# logi-cam.net
KiCad netlist of a schematic drawn in Altium Designer
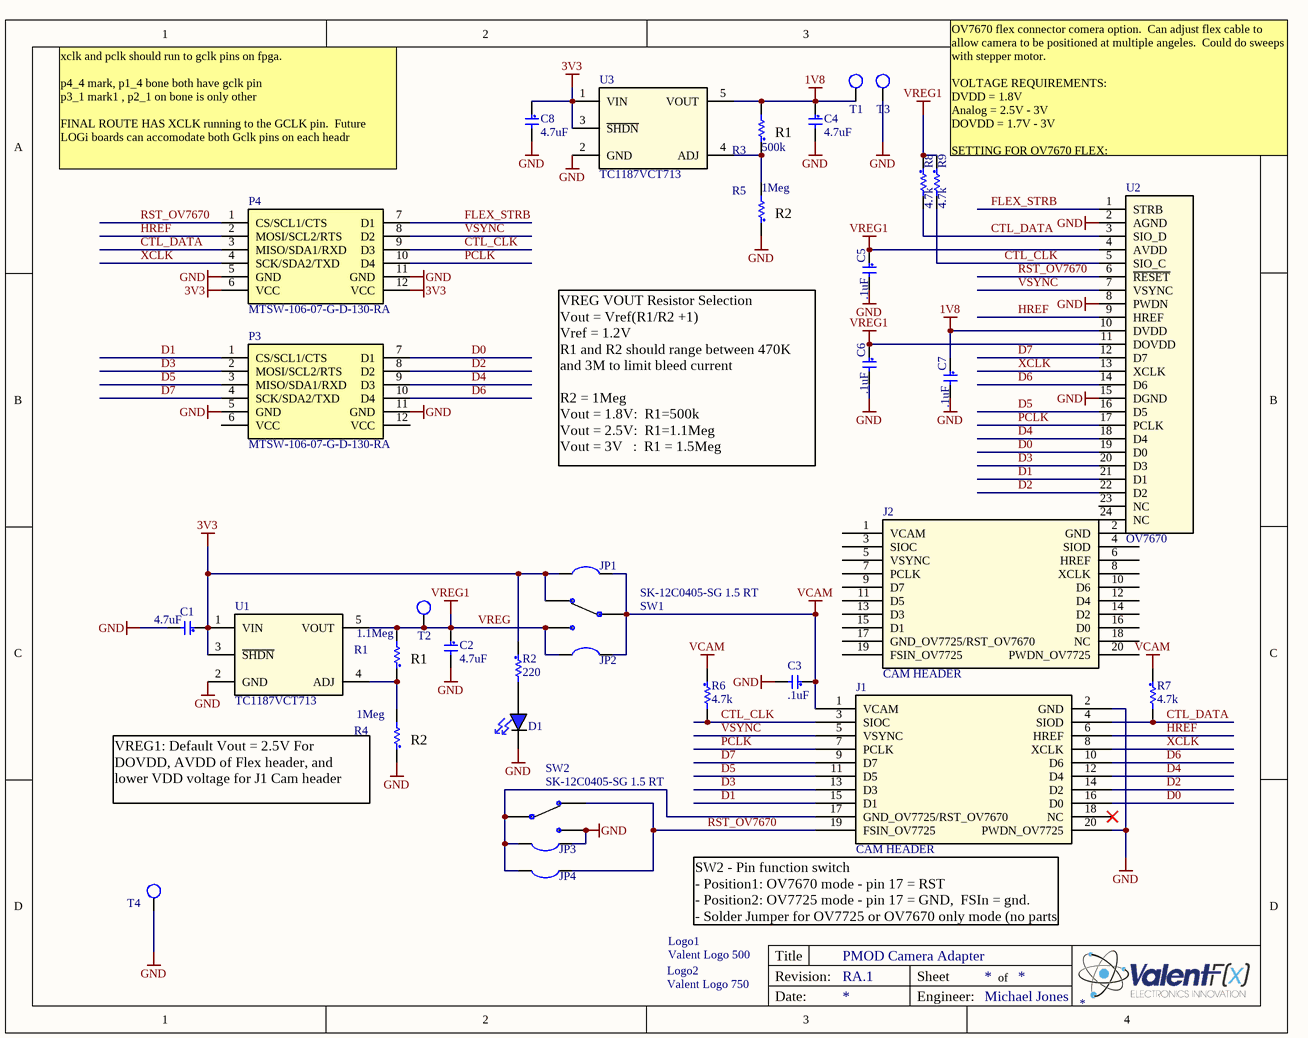
[diagram p0: logi-cam.SchDoc]

(export (version "E")
  (design (tool "Eeschema 10.0.6"))
  (components
    (comp (ref "C1")
      (value "4.7uF")
      (footprint "mRCL:C0603")
      (description "4.7uF 10volts Y5V +80-20% (MLCC) - SMD/SMT 0603")
      (fields
        (field (name "MANUFACTURER") "Murata")
        (field (name "MANUFACTURER PART NUMBER") "GRM188F51A475ZE20D")
      )
      (libsource (lib "mCapacitors") (part "C0603 - GRM188F51A475ZE20D"))
    )
    (comp (ref "C2")
      (value "4.7uF")
      (footprint "mRCL:C0603")
      (description "4.7uF 10volts Y5V +80-20% (MLCC) - SMD/SMT 0603")
      (fields
        (field (name "MANUFACTURER") "Murata")
        (field (name "MANUFACTURER PART NUMBER") "GRM188F51A475ZE20D")
      )
      (libsource (lib "mCapacitors") (part "C0603 - GRM188F51A475ZE20D"))
    )
    (comp (ref "C3")
      (value ".1uF")
      (footprint "mRCL:C0603")
      (description ".10uF X7R 20% (MLCC) - SMD/SMT 0603 25volts")
      (fields (field (name "MANUFACTURER") "TDK") (field (name "MANUFACTURER PART NUMBER") "C1608X7R1E104MT"))
      (libsource (lib "mCapacitors") (part "C0603 - C1608X7R1E104MT"))
    )
    (comp (ref "C4")
      (value "4.7uF")
      (footprint "mRCL:C0603")
      (description "4.7uF 10volts Y5V +80-20% (MLCC) - SMD/SMT 0603")
      (fields
        (field (name "MANUFACTURER") "Murata")
        (field (name "MANUFACTURER PART NUMBER") "GRM188F51A475ZE20D")
      )
      (libsource (lib "mCapacitors") (part "C0603 - GRM188F51A475ZE20D"))
    )
    (comp (ref "C5")
      (value ".1uF")
      (footprint "mRCL:C0603")
      (description ".10uF X7R 20% (MLCC) - SMD/SMT 0603 25volts")
      (fields (field (name "MANUFACTURER") "TDK") (field (name "MANUFACTURER PART NUMBER") "C1608X7R1E104MT"))
      (libsource (lib "mCapacitors") (part "C0603 - C1608X7R1E104MT"))
    )
    (comp (ref "C6")
      (value ".1uF")
      (footprint "mRCL:C0603")
      (description ".10uF X7R 20% (MLCC) - SMD/SMT 0603 25volts")
      (fields (field (name "MANUFACTURER") "TDK") (field (name "MANUFACTURER PART NUMBER") "C1608X7R1E104MT"))
      (libsource (lib "mCapacitors") (part "C0603 - C1608X7R1E104MT"))
    )
    (comp (ref "C7")
      (value ".1uF")
      (footprint "mRCL:C0603")
      (description ".10uF X7R 20% (MLCC) - SMD/SMT 0603 25volts")
      (fields (field (name "MANUFACTURER") "TDK") (field (name "MANUFACTURER PART NUMBER") "C1608X7R1E104MT"))
      (libsource (lib "mCapacitors") (part "C0603 - C1608X7R1E104MT"))
    )
    (comp (ref "C8")
      (value "4.7uF")
      (footprint "mRCL:C0603")
      (description "4.7uF 10volts Y5V +80-20% (MLCC) - SMD/SMT 0603")
      (fields
        (field (name "MANUFACTURER") "Murata")
        (field (name "MANUFACTURER PART NUMBER") "GRM188F51A475ZE20D")
      )
      (libsource (lib "mCapacitors") (part "C0603 - GRM188F51A475ZE20D"))
    )
    (comp (ref "D1")
      (value "BLUE LED0603")
      (footprint "LED_0603 - BLUE")
      (description "BLUE Standard LED - SMD Blue 470nm 40mcd 20mA")
      (fields
        (field (name "MANUFACTURER") "Harvatek International")
        (field (name "MANUFACTURER PART NUMBER") "HT-193NB-5589")
      )
      (libsource (lib "mDiode") (part "LED0603 - HT-193NB-5589"))
    )
    (comp (ref "J1")
      (value "CAM HEADER")
      (footprint "HEADER_10x2_40_100 1-3-5 THRU DIP")
      (description "CMOS CAMERA HEADER")
      (libsource (lib "mModule") (part "CAM - DUAL CAMERA HEADER_1"))
    )
    (comp (ref "J2")
      (value "CAM HEADER")
      (footprint "HEADER_10x2_40_100 1-3-5 THRU DIP")
      (description "CMOS CAMERA HEADER")
      (libsource (lib "mModule") (part "CAM - DUAL CAMERA HEADER_1"))
    )
    (comp (ref "JP1")
      (value "Solder Jumper")
      (footprint "SOLDER_JUMPER")
      (description "Solder/Configuration Jumper")
      (fields (field (name "MANUFACTURER") "n/a"))
      (libsource (lib "mConnector") (part "Solder Jumper"))
    )
    (comp (ref "JP2")
      (value "Solder Jumper")
      (footprint "SOLDER_JUMPER")
      (description "Solder/Configuration Jumper")
      (fields (field (name "MANUFACTURER") "n/a"))
      (libsource (lib "mConnector") (part "Solder Jumper"))
    )
    (comp (ref "JP3")
      (value "Solder Jumper")
      (footprint "SOLDER_JUMPER")
      (description "Solder/Configuration Jumper")
      (fields (field (name "MANUFACTURER") "n/a"))
      (libsource (lib "mConnector") (part "Solder Jumper"))
    )
    (comp (ref "JP4")
      (value "Solder Jumper")
      (footprint "SOLDER_JUMPER")
      (description "Solder/Configuration Jumper")
      (fields (field (name "MANUFACTURER") "n/a"))
      (libsource (lib "mConnector") (part "Solder Jumper"))
    )
    (comp (ref "Logo1")
      (value "Valent Logo 500")
      (footprint "ValentFX_500")
      (libsource (lib "mLogos") (part "Valent Logo 500"))
    )
    (comp (ref "Logo2")
      (value "Valent Logo 750")
      (footprint "ValentFX_750")
      (libsource (lib "mLogos") (part "Valent Logo 750"))
    )
    (comp (ref "P3")
      (value "MTSW-106-07-G-D-130-RA")
      (footprint "mconnector:PMOD HEADER - Male")
      (description "Samtec Male Conn Unshrouded Header HDR 12 POS 2.54mm Solder RA Thru-Hole")
      (fields (field (name "MANUFACTURER") "Samtec"))
      (libsource (lib "mConnector") (part "P-MOD - MTSW-106-07-G-D-130-RA"))
    )
    (comp (ref "P4")
      (value "MTSW-106-07-G-D-130-RA")
      (footprint "mconnector:PMOD HEADER - Male")
      (description "Samtec Male Conn Unshrouded Header HDR 12 POS 2.54mm Solder RA Thru-Hole")
      (fields (field (name "MANUFACTURER") "Samtec"))
      (libsource (lib "mConnector") (part "P-MOD - MTSW-106-07-G-D-130-RA"))
    )
    (comp (ref "R1")
      (value "1.1Meg")
      (footprint "R0805")
      (description "1Kohms 1% Thick Film Resistors - SMD 0603  Tol")
      (fields
        (field (name "MANUFACTURER") "Panasonic Electronic Components")
        (field (name "MANUFACTURER PART NUMBER") "ERJ-3EKF1001V")
      )
      (libsource (lib "mResistors") (part "R0603 - ERJ-3EKF1001V"))
    )
    (comp (ref "R2")
      (value "220")
      (footprint "mRCL:R0603")
      (description "220 - thick Film Resistors - SMD 0603 220ohms 1% Tol")
      (fields
        (field (name "MANUFACTURER") "Panasonic - ECG")
        (field (name "MANUFACTURER PART NUMBER") "ERJ-3EKF2200V")
      )
      (libsource (lib "mResistors") (part "R0603 - ERJ-3EKF2200V"))
    )
    (comp (ref "R3")
      (value "500k")
      (footprint "R0805")
      (description "1Kohms 1% Thick Film Resistors - SMD 0603  Tol")
      (fields
        (field (name "MANUFACTURER") "Panasonic Electronic Components")
        (field (name "MANUFACTURER PART NUMBER") "ERJ-3EKF1001V")
      )
      (libsource (lib "mResistors") (part "R0603 - ERJ-3EKF1001V"))
    )
    (comp (ref "R4")
      (value "1Meg")
      (footprint "R0805")
      (description "1Kohms 1% Thick Film Resistors - SMD 0603  Tol")
      (fields
        (field (name "MANUFACTURER") "Panasonic Electronic Components")
        (field (name "MANUFACTURER PART NUMBER") "ERJ-3EKF1001V")
      )
      (libsource (lib "mResistors") (part "R0603 - ERJ-3EKF1001V"))
    )
    (comp (ref "R5")
      (value "1Meg")
      (footprint "R0805")
      (description "1Kohms 1% Thick Film Resistors - SMD 0603  Tol")
      (fields
        (field (name "MANUFACTURER") "Panasonic Electronic Components")
        (field (name "MANUFACTURER PART NUMBER") "ERJ-3EKF1001V")
      )
      (libsource (lib "mResistors") (part "R0603 - ERJ-3EKF1001V"))
    )
    (comp (ref "R6")
      (value "4.7k")
      (footprint "mRCL:R0603")
      (description "4.7k Thick Film Resistors - SMD 1/10watt 4.7Kohms 1%")
      (fields
        (field (name "MANUFACTURER") "Vishay Dale")
        (field (name "MANUFACTURER PART NUMBER") "CRCW06034K70FKEA")
      )
      (libsource (lib "mResistors") (part "R0603 - CRCW06034K70FKEA"))
    )
    (comp (ref "R7")
      (value "4.7k")
      (footprint "mRCL:R0603")
      (description "4.7k Thick Film Resistors - SMD 1/10watt 4.7Kohms 1%")
      (fields
        (field (name "MANUFACTURER") "Vishay Dale")
        (field (name "MANUFACTURER PART NUMBER") "CRCW06034K70FKEA")
      )
      (libsource (lib "mResistors") (part "R0603 - CRCW06034K70FKEA"))
    )
    (comp (ref "R8")
      (value "4.7k")
      (footprint "mRCL:R0603")
      (description "4.7k Thick Film Resistors - SMD 1/10watt 4.7Kohms 1%")
      (fields
        (field (name "MANUFACTURER") "Vishay Dale")
        (field (name "MANUFACTURER PART NUMBER") "CRCW06034K70FKEA")
      )
      (libsource (lib "mResistors") (part "R0603 - CRCW06034K70FKEA"))
    )
    (comp (ref "R9")
      (value "4.7k")
      (footprint "mRCL:R0603")
      (description "4.7k Thick Film Resistors - SMD 1/10watt 4.7Kohms 1%")
      (fields
        (field (name "MANUFACTURER") "Vishay Dale")
        (field (name "MANUFACTURER PART NUMBER") "CRCW06034K70FKEA")
      )
      (libsource (lib "mResistors") (part "R0603 - CRCW06034K70FKEA"))
    )
    (comp (ref "SW1")
      (value "SK-12C0405-SG 1.5 RT")
      (footprint "SW - SK-12C0405-SG 1.5 RT")
      (description "Slide Switches SPDT 0.3 Amp at 4 V")
      (fields (field (name "MANUFACTURER") "C&K Components"))
      (libsource (lib "mElectroMechanical") (part "SW - SK-12C0405-SG 1.5 RT"))
    )
    (comp (ref "SW2")
      (value "SK-12C0405-SG 1.5 RT")
      (footprint "SW - SK-12C0405-SG 1.5 RT")
      (description "Slide Switches SPDT 0.3 Amp at 4 V")
      (fields (field (name "MANUFACTURER") "C&K Components"))
      (libsource (lib "mElectroMechanical") (part "SW - SK-12C0405-SG 1.5 RT"))
    )
    (comp (ref "T1")
      (value "Test Point")
      (footprint "Tp 25-40")
      (description "Test Point Smaller Symbol")
      (libsource (lib "mConnector") (part "Test Point 2"))
    )
    (comp (ref "T2")
      (value "Test Point")
      (footprint "Tp 25-40")
      (description "Test Point Smaller Symbol")
      (libsource (lib "mConnector") (part "Test Point 2"))
    )
    (comp (ref "T3")
      (value "Test Point")
      (footprint "Tp 25-40")
      (description "Test Point Smaller Symbol")
      (libsource (lib "mConnector") (part "Test Point 2"))
    )
    (comp (ref "T4")
      (value "Test Point")
      (footprint "Tp 25-40")
      (description "Test Point Smaller Symbol")
      (libsource (lib "mConnector") (part "Test Point 2"))
    )
    (comp (ref "U1")
      (value "TC1187VCT713")
      (footprint "SOT95P280X145-5N - TC2054")
      (description "IC REG LDO ADJ .15A SOT23A-5")
      (fields (field (name "MANUFACTURER") "Microchip Technology"))
      (libsource (lib "mIC") (part "REG - TC1187VCT713"))
    )
    (comp (ref "U2")
      (value "OV7670")
      (footprint "OV7670")
      (description "OV7670 - 24 PIN FFC")
      (libsource (lib "mModule") (part "OV7670"))
    )
    (comp (ref "U3")
      (value "TC1187VCT713")
      (footprint "SOT95P280X145-5N - TC2054")
      (description "IC REG LDO ADJ .15A SOT23A-5")
      (fields (field (name "MANUFACTURER") "Microchip Technology"))
      (libsource (lib "mIC") (part "REG - TC1187VCT713"))
    )
  )
  (nets
    (net (code "1") (name "/CTL_CLK") (class "Default")
      (node (ref "J1") (pin "3") (pinfunction "SIOC_3") (pintype "passive"))
      (node (ref "P4") (pin "9") (pinfunction "D3_9") (pintype "power_in"))
      (node (ref "R6") (pin "2") (pinfunction "2_2") (pintype "passive"))
      (node (ref "R9") (pin "2") (pinfunction "2_2") (pintype "passive"))
      (node (ref "U2") (pin "5") (pinfunction "SIO_C_5") (pintype "passive"))
    )
    (net (code "2") (name "/CTL_DATA") (class "Default")
      (node (ref "J1") (pin "4") (pinfunction "SIOD_4") (pintype "passive"))
      (node (ref "P4") (pin "3") (pinfunction "MISO/SDA1/RXD_3") (pintype "power_in"))
      (node (ref "R7") (pin "2") (pinfunction "2_2") (pintype "passive"))
      (node (ref "R8") (pin "2") (pinfunction "2_2") (pintype "passive"))
      (node (ref "U2") (pin "3") (pinfunction "SIO_D_3") (pintype "passive"))
    )
    (net (code "3") (name "/D0") (class "Default")
      (node (ref "J1") (pin "16") (pinfunction "D0_16") (pintype "passive"))
      (node (ref "P3") (pin "7") (pinfunction "D1_7") (pintype "power_in"))
      (node (ref "U2") (pin "19") (pinfunction "D0_19") (pintype "passive"))
    )
    (net (code "4") (name "/D1") (class "Default")
      (node (ref "J1") (pin "15") (pinfunction "D1_15") (pintype "passive"))
      (node (ref "P3") (pin "1") (pinfunction "CS/SCL1/CTS_1") (pintype "power_in"))
      (node (ref "U2") (pin "21") (pinfunction "D1_21") (pintype "passive"))
    )
    (net (code "5") (name "/D2") (class "Default")
      (node (ref "J1") (pin "14") (pinfunction "D2_14") (pintype "passive"))
      (node (ref "P3") (pin "8") (pinfunction "D2_8") (pintype "power_in"))
      (node (ref "U2") (pin "22") (pinfunction "D2_22") (pintype "passive"))
    )
    (net (code "6") (name "/D3") (class "Default")
      (node (ref "J1") (pin "13") (pinfunction "D3_13") (pintype "passive"))
      (node (ref "P3") (pin "2") (pinfunction "MOSI/SCL2/RTS_2") (pintype "power_in"))
      (node (ref "U2") (pin "20") (pinfunction "D3_20") (pintype "passive"))
    )
    (net (code "7") (name "/D4") (class "Default")
      (node (ref "J1") (pin "12") (pinfunction "D4_12") (pintype "passive"))
      (node (ref "P3") (pin "9") (pinfunction "D3_9") (pintype "power_in"))
      (node (ref "U2") (pin "18") (pinfunction "D4_18") (pintype "passive"))
    )
    (net (code "8") (name "/D5") (class "Default")
      (node (ref "J1") (pin "11") (pinfunction "D5_11") (pintype "passive"))
      (node (ref "P3") (pin "3") (pinfunction "MISO/SDA1/RXD_3") (pintype "power_in"))
      (node (ref "U2") (pin "16") (pinfunction "D5_16") (pintype "passive"))
    )
    (net (code "9") (name "/D6") (class "Default")
      (node (ref "J1") (pin "10") (pinfunction "D6_10") (pintype "passive"))
      (node (ref "P3") (pin "10") (pinfunction "D4_10") (pintype "power_in"))
      (node (ref "U2") (pin "14") (pinfunction "D6_14") (pintype "passive"))
    )
    (net (code "10") (name "/D7") (class "Default")
      (node (ref "J1") (pin "9") (pinfunction "D7_9") (pintype "passive"))
      (node (ref "P3") (pin "4") (pinfunction "SCK/SDA2/TXD_4") (pintype "power_in"))
      (node (ref "U2") (pin "12") (pinfunction "D7_12") (pintype "passive"))
    )
    (net (code "11") (name "/FLEX_STRB") (class "Default")
      (node (ref "P4") (pin "7") (pinfunction "D1_7") (pintype "power_in"))
      (node (ref "U2") (pin "1") (pinfunction "STRB_1") (pintype "passive"))
    )
    (net (code "12") (name "/HREF") (class "Default")
      (node (ref "J1") (pin "6") (pinfunction "HREF_6") (pintype "passive"))
      (node (ref "P4") (pin "2") (pinfunction "MOSI/SCL2/RTS_2") (pintype "power_in"))
      (node (ref "U2") (pin "9") (pinfunction "HREF_9") (pintype "passive"))
    )
    (net (code "13") (name "/PCLK") (class "Default")
      (node (ref "J1") (pin "7") (pinfunction "PCLK_7") (pintype "passive"))
      (node (ref "P4") (pin "10") (pinfunction "D4_10") (pintype "power_in"))
      (node (ref "U2") (pin "17") (pinfunction "PCLK_17") (pintype "passive"))
    )
    (net (code "14") (name "/RST_OV7670") (class "Default")
      (node (ref "J1") (pin "19") (pinfunction "FSIN_OV7725_19") (pintype "passive"))
      (node (ref "JP4") (pin "1") (pinfunction "1_1") (pintype "passive"))
      (node (ref "P4") (pin "1") (pinfunction "CS/SCL1/CTS_1") (pintype "power_in"))
      (node (ref "SW2") (pin "2") (pinfunction "2_2") (pintype "passive"))
      (node (ref "U2") (pin "6") (pinfunction "~{RESET}_6") (pintype "passive"))
    )
    (net (code "15") (name "/VSYNC") (class "Default")
      (node (ref "J1") (pin "5") (pinfunction "VSYNC_5") (pintype "passive"))
      (node (ref "P4") (pin "8") (pinfunction "D2_8") (pintype "power_in"))
      (node (ref "U2") (pin "7") (pinfunction "VSYNC_7") (pintype "passive"))
    )
    (net (code "16") (name "/XCLK") (class "Default")
      (node (ref "J1") (pin "8") (pinfunction "XCLK_8") (pintype "passive"))
      (node (ref "P4") (pin "4") (pinfunction "SCK/SDA2/TXD_4") (pintype "power_in"))
      (node (ref "U2") (pin "13") (pinfunction "XCLK_13") (pintype "passive"))
    )
    (net (code "17") (name "1V8") (class "Default")
      (node (ref "C4") (pin "1") (pinfunction "1_1") (pintype "passive"))
      (node (ref "C7") (pin "1") (pinfunction "1_1") (pintype "passive"))
      (node (ref "R3") (pin "2") (pinfunction "2_2") (pintype "passive"))
      (node (ref "T1") (pin "1") (pinfunction "1_1") (pintype "passive"))
      (node (ref "U2") (pin "10") (pinfunction "DVDD_10") (pintype "passive"))
      (node (ref "U3") (pin "5") (pinfunction "VOUT_5") (pintype "passive"))
    )
    (net (code "18") (name "3V3") (class "Default")
      (node (ref "C1") (pin "1") (pinfunction "1_1") (pintype "passive"))
      (node (ref "C8") (pin "1") (pinfunction "1_1") (pintype "passive"))
      (node (ref "JP1") (pin "1") (pinfunction "1_1") (pintype "passive"))
      (node (ref "P4") (pin "12") (pinfunction "VCC_12") (pintype "power_in"))
      (node (ref "P4") (pin "6") (pinfunction "VCC_6") (pintype "power_in"))
      (node (ref "R2") (pin "1") (pinfunction "1_1") (pintype "passive"))
      (node (ref "SW1") (pin "2") (pinfunction "2_2") (pintype "passive"))
      (node (ref "U1") (pin "1") (pinfunction "VIN_1") (pintype "passive"))
      (node (ref "U1") (pin "3") (pinfunction "~{SHDN}_3") (pintype "passive"))
      (node (ref "U3") (pin "1") (pinfunction "VIN_1") (pintype "passive"))
      (node (ref "U3") (pin "3") (pinfunction "~{SHDN}_3") (pintype "passive"))
    )
    (net (code "19") (name "GND") (class "Default")
      (node (ref "C1") (pin "2") (pinfunction "2_2") (pintype "passive"))
      (node (ref "C2") (pin "2") (pinfunction "2_2") (pintype "passive"))
      (node (ref "C3") (pin "2") (pinfunction "2_2") (pintype "passive"))
      (node (ref "C4") (pin "2") (pinfunction "2_2") (pintype "passive"))
      (node (ref "C5") (pin "2") (pinfunction "2_2") (pintype "passive"))
      (node (ref "C6") (pin "2") (pinfunction "2_2") (pintype "passive"))
      (node (ref "C7") (pin "2") (pinfunction "2_2") (pintype "passive"))
      (node (ref "C8") (pin "2") (pinfunction "2_2") (pintype "passive"))
      (node (ref "D1") (pin "C") (pinfunction "C_C") (pintype "passive"))
      (node (ref "J1") (pin "2") (pinfunction "GND_2") (pintype "passive"))
      (node (ref "J1") (pin "20") (pinfunction "PWDN_OV7725_20") (pintype "passive"))
      (node (ref "JP3") (pin "1") (pinfunction "1_1") (pintype "passive"))
      (node (ref "P3") (pin "11") (pinfunction "GND_11") (pintype "power_in"))
      (node (ref "P3") (pin "5") (pinfunction "GND_5") (pintype "power_in"))
      (node (ref "P4") (pin "11") (pinfunction "GND_11") (pintype "power_in"))
      (node (ref "P4") (pin "5") (pinfunction "GND_5") (pintype "power_in"))
      (node (ref "R4") (pin "1") (pinfunction "1_1") (pintype "passive"))
      (node (ref "R5") (pin "1") (pinfunction "1_1") (pintype "passive"))
      (node (ref "SW2") (pin "3") (pinfunction "3_3") (pintype "passive"))
      (node (ref "T3") (pin "1") (pinfunction "1_1") (pintype "passive"))
      (node (ref "T4") (pin "1") (pinfunction "1_1") (pintype "passive"))
      (node (ref "U1") (pin "2") (pinfunction "GND_2") (pintype "passive"))
      (node (ref "U2") (pin "15") (pinfunction "DGND_15") (pintype "passive"))
      (node (ref "U2") (pin "2") (pinfunction "AGND_2") (pintype "passive"))
      (node (ref "U2") (pin "8") (pinfunction "PWDN_8") (pintype "passive"))
      (node (ref "U3") (pin "2") (pinfunction "GND_2") (pintype "passive"))
    )
    (net (code "20") (name "Net-(D1-PadA)") (class "Default")
      (node (ref "D1") (pin "A") (pinfunction "A_A") (pintype "passive"))
      (node (ref "R2") (pin "2") (pinfunction "2_2") (pintype "passive"))
    )
    (net (code "21") (name "Net-(J1-GND_OV7725{slash}RST_OV7670)") (class "Default")
      (node (ref "J1") (pin "17") (pinfunction "GND_OV7725/RST_OV7670_17") (pintype "passive"))
      (node (ref "JP3") (pin "2") (pinfunction "2_2") (pintype "passive"))
      (node (ref "JP4") (pin "2") (pinfunction "2_2") (pintype "passive"))
      (node (ref "SW2") (pin "1") (pinfunction "1_1") (pintype "passive"))
    )
    (net (code "22") (name "Net-(U1-ADJ)") (class "Default")
      (node (ref "R1") (pin "1") (pinfunction "1_1") (pintype "passive"))
      (node (ref "R4") (pin "2") (pinfunction "2_2") (pintype "passive"))
      (node (ref "U1") (pin "4") (pinfunction "ADJ_4") (pintype "passive"))
    )
    (net (code "23") (name "Net-(U3-ADJ)") (class "Default")
      (node (ref "R3") (pin "1") (pinfunction "1_1") (pintype "passive"))
      (node (ref "R5") (pin "2") (pinfunction "2_2") (pintype "passive"))
      (node (ref "U3") (pin "4") (pinfunction "ADJ_4") (pintype "passive"))
    )
    (net (code "24") (name "VCAM") (class "Default")
      (node (ref "C3") (pin "1") (pinfunction "1_1") (pintype "passive"))
      (node (ref "J1") (pin "1") (pinfunction "VCAM_1") (pintype "passive"))
      (node (ref "JP1") (pin "2") (pinfunction "2_2") (pintype "passive"))
      (node (ref "JP2") (pin "2") (pinfunction "2_2") (pintype "passive"))
      (node (ref "R6") (pin "1") (pinfunction "1_1") (pintype "passive"))
      (node (ref "R7") (pin "1") (pinfunction "1_1") (pintype "passive"))
      (node (ref "SW1") (pin "1") (pinfunction "1_1") (pintype "passive"))
    )
    (net (code "25") (name "VREG1") (class "Default")
      (node (ref "C2") (pin "1") (pinfunction "1_1") (pintype "passive"))
      (node (ref "C5") (pin "1") (pinfunction "1_1") (pintype "passive"))
      (node (ref "C6") (pin "1") (pinfunction "1_1") (pintype "passive"))
      (node (ref "JP2") (pin "1") (pinfunction "1_1") (pintype "passive"))
      (node (ref "R1") (pin "2") (pinfunction "2_2") (pintype "passive"))
      (node (ref "R8") (pin "1") (pinfunction "1_1") (pintype "passive"))
      (node (ref "R9") (pin "1") (pinfunction "1_1") (pintype "passive"))
      (node (ref "SW1") (pin "3") (pinfunction "3_3") (pintype "passive"))
      (node (ref "T2") (pin "1") (pinfunction "1_1") (pintype "passive"))
      (node (ref "U1") (pin "5") (pinfunction "VOUT_5") (pintype "passive"))
      (node (ref "U2") (pin "11") (pinfunction "DOVDD_11") (pintype "passive"))
      (node (ref "U2") (pin "4") (pinfunction "AVDD_4") (pintype "passive"))
    )
    (net (code "26") (name "unconnected-(J1-NC-Pad18)") (class "Default")
      (node (ref "J1") (pin "18") (pinfunction "NC_18") (pintype "passive+no_connect"))
    )
    (net (code "27") (name "unconnected-(J2-D0-Pad16)") (class "Default")
      (node (ref "J2") (pin "16") (pinfunction "D0_16") (pintype "passive"))
    )
    (net (code "28") (name "unconnected-(J2-D1-Pad15)") (class "Default")
      (node (ref "J2") (pin "15") (pinfunction "D1_15") (pintype "passive"))
    )
    (net (code "29") (name "unconnected-(J2-D2-Pad14)") (class "Default")
      (node (ref "J2") (pin "14") (pinfunction "D2_14") (pintype "passive"))
    )
    (net (code "30") (name "unconnected-(J2-D3-Pad13)") (class "Default")
      (node (ref "J2") (pin "13") (pinfunction "D3_13") (pintype "passive"))
    )
    (net (code "31") (name "unconnected-(J2-D4-Pad12)") (class "Default")
      (node (ref "J2") (pin "12") (pinfunction "D4_12") (pintype "passive"))
    )
    (net (code "32") (name "unconnected-(J2-D5-Pad11)") (class "Default")
      (node (ref "J2") (pin "11") (pinfunction "D5_11") (pintype "passive"))
    )
    (net (code "33") (name "unconnected-(J2-D6-Pad10)") (class "Default")
      (node (ref "J2") (pin "10") (pinfunction "D6_10") (pintype "passive"))
    )
    (net (code "34") (name "unconnected-(J2-D7-Pad9)") (class "Default")
      (node (ref "J2") (pin "9") (pinfunction "D7_9") (pintype "passive"))
    )
    (net (code "35") (name "unconnected-(J2-FSIN_OV7725-Pad19)") (class "Default")
      (node (ref "J2") (pin "19") (pinfunction "FSIN_OV7725_19") (pintype "passive"))
    )
    (net (code "36") (name "unconnected-(J2-GND-Pad2)") (class "Default")
      (node (ref "J2") (pin "2") (pinfunction "GND_2") (pintype "passive"))
    )
    (net (code "37") (name "unconnected-(J2-GND_OV7725{slash}RST_OV7670-Pad17)") (class "Default")
      (node (ref "J2") (pin "17") (pinfunction "GND_OV7725/RST_OV7670_17") (pintype "passive"))
    )
    (net (code "38") (name "unconnected-(J2-HREF-Pad6)") (class "Default")
      (node (ref "J2") (pin "6") (pinfunction "HREF_6") (pintype "passive"))
    )
    (net (code "39") (name "unconnected-(J2-NC-Pad18)") (class "Default")
      (node (ref "J2") (pin "18") (pinfunction "NC_18") (pintype "passive"))
    )
    (net (code "40") (name "unconnected-(J2-PCLK-Pad7)") (class "Default")
      (node (ref "J2") (pin "7") (pinfunction "PCLK_7") (pintype "passive"))
    )
    (net (code "41") (name "unconnected-(J2-PWDN_OV7725-Pad20)") (class "Default")
      (node (ref "J2") (pin "20") (pinfunction "PWDN_OV7725_20") (pintype "passive"))
    )
    (net (code "42") (name "unconnected-(J2-SIOC-Pad3)") (class "Default")
      (node (ref "J2") (pin "3") (pinfunction "SIOC_3") (pintype "passive"))
    )
    (net (code "43") (name "unconnected-(J2-SIOD-Pad4)") (class "Default")
      (node (ref "J2") (pin "4") (pinfunction "SIOD_4") (pintype "passive"))
    )
    (net (code "44") (name "unconnected-(J2-VCAM-Pad1)") (class "Default")
      (node (ref "J2") (pin "1") (pinfunction "VCAM_1") (pintype "passive"))
    )
    (net (code "45") (name "unconnected-(J2-VSYNC-Pad5)") (class "Default")
      (node (ref "J2") (pin "5") (pinfunction "VSYNC_5") (pintype "passive"))
    )
    (net (code "46") (name "unconnected-(J2-XCLK-Pad8)") (class "Default")
      (node (ref "J2") (pin "8") (pinfunction "XCLK_8") (pintype "passive"))
    )
    (net (code "47") (name "unconnected-(P3-VCC-Pad6)") (class "Default")
      (node (ref "P3") (pin "6") (pinfunction "VCC_6") (pintype "power_in"))
    )
    (net (code "48") (name "unconnected-(P3-VCC-Pad12)") (class "Default")
      (node (ref "P3") (pin "12") (pinfunction "VCC_12") (pintype "power_in"))
    )
    (net (code "49") (name "unconnected-(U2-NC-Pad23)") (class "Default")
      (node (ref "U2") (pin "23") (pinfunction "NC_23") (pintype "passive"))
    )
    (net (code "50") (name "unconnected-(U2-NC-Pad24)") (class "Default")
      (node (ref "U2") (pin "24") (pinfunction "NC_24") (pintype "passive"))
    )
  )
)
